# LCD-43.net
KiCad netlist of a schematic drawn in Altium Designer
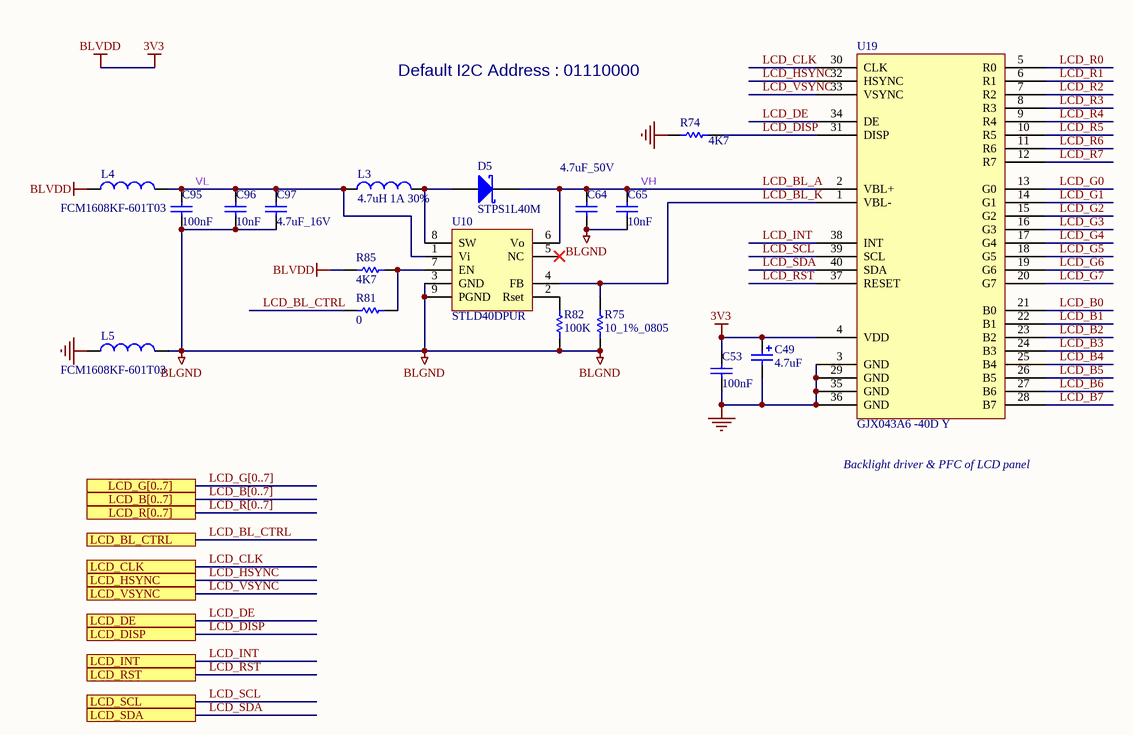
[diagram p0: LCD-43.SchDoc]

(export (version "E")
  (design (tool "Eeschema 10.0.6"))
  (components
    (comp (ref "C49")
      (value "4.7uF")
      (footprint "TAN-A")
      (description "Polarized Capacitor,4.7uF,16V,10%,typeA,AVX")
      (libsource (lib "MCD_TOOLS") (part "Cap_4.7uF_POL_10%_TANA"))
    )
    (comp (ref "C53")
      (value "100nF")
      (footprint "0402C")
      (description "Capacitor,100nF,16V,X7R,10%,0402,YAGEO")
      (libsource (lib "MCD_TOOLS") (part "Cap_100nF_X7R_10%_0402"))
    )
    (comp (ref "C64")
      (value "4.7uF_50V")
      (footprint "1206C")
      (description "Capacitor,4.7uF,50V, X7R,10%,1206,AVX")
      (libsource (lib "MCD_TOOLS") (part "Cap_4.7uF_X7R_10%_1206"))
    )
    (comp (ref "C65")
      (value "10nF")
      (footprint "0603C")
      (description "Capacitor,10nF,50V,X7R,10%,0603,YAGEO")
      (libsource (lib "MCD_TOOLS") (part "Cap_10nF_X7R_10%_0603"))
    )
    (comp (ref "C95")
      (value "100nF")
      (footprint "0603C")
      (description "Capacitor,100nF,16V,X7R,10%,0603,YAGEO")
      (libsource (lib "MCD_TOOLS") (part "Cap_100nF_X7R_10%_0603"))
    )
    (comp (ref "C96")
      (value "10nF")
      (footprint "0603C")
      (description "Capacitor,10nF,50V,X7R,10%,0603,YAGEO")
      (libsource (lib "MCD_TOOLS") (part "Cap_10nF_X7R_10%_0603"))
    )
    (comp (ref "C97")
      (value "4.7uF_16V")
      (footprint "1206C")
      (description "Capacitor,4.7uF,16V, X5R,10%,1206,AVX")
      (libsource (lib "MCD_TOOLS") (part "Cap_4.7uF_X5R_10%_1206"))
    )
    (comp (ref "D5")
      (value "STPS1L40M")
      (footprint "DO216-AA")
      (description "Low Drop power Schottky rectifier(1A, 40V, 0.4V)")
      (libsource (lib "MCD_TOOLS") (part "STPS1L40M"))
    )
    (comp (ref "L3")
      (value "4.7uH 1A 30%")
      (footprint "1210L")
      (description "FIXED IND 4.7UH 1A 180 MOHM 30% SMD")
      (libsource (lib "MCD_TOOLS") (part "Ind_4.7uH_1A_30%"))
    )
    (comp (ref "L4")
      (value "FCM1608KF-601T03")
      (footprint "0603L")
      (description "Bead,600R,350mA,0603,FCM1608KF-601T03,Tai-tech")
      (libsource (lib "MCD_TOOLS") (part "BEAD_600R_350MA_0603"))
    )
    (comp (ref "L5")
      (value "FCM1608KF-601T03")
      (footprint "0603L")
      (description "Bead,600R,350mA,0603,FCM1608KF-601T03,Tai-tech")
      (libsource (lib "MCD_TOOLS") (part "BEAD_600R_350MA_0603"))
    )
    (comp (ref "R74")
      (value "4K7")
      (footprint "0402R")
      (description "Resistor,4K7,0402,1%,YAGEO")
      (libsource (lib "MCD_TOOLS") (part "Res_4K7_1%_0402"))
    )
    (comp (ref "R75")
      (value "10_1%_0805")
      (footprint "0805R")
      (description "Resistor,10,0805,1%,Stackpole,1/4W")
      (libsource (lib "MCD_TOOLS") (part "Res_10_1%_0805"))
    )
    (comp (ref "R81")
      (value "0")
      (footprint "0402R")
      (description "Resistor,0,0402,5%,YAGEO")
      (libsource (lib "MCD_TOOLS") (part "Res_0_5%_0402"))
    )
    (comp (ref "R82")
      (value "100K")
      (footprint "0402R")
      (description "Resistor,100K,0402,1%,YAGEO")
      (libsource (lib "MCD_TOOLS") (part "Res_100K_1%_0402"))
    )
    (comp (ref "R85")
      (value "4K7")
      (footprint "0402R")
      (description "Resistor,4K7,0402,1%,YAGEO")
      (libsource (lib "MCD_TOOLS") (part "Res_4K7_1%_0402"))
    )
    (comp (ref "U10")
      (value "STLD40DPUR")
      (footprint "QFN8_0R65_3X3_ST")
      (description "White LED power supply for large display backlight, QFN8")
      (libsource (lib "MCD_TOOLS") (part "STLD40DPUR"))
    )
    (comp (ref "U19")
      (value "GJX043A6 -40D Y")
      (footprint "LCD_Kunjian_ HT043C_40P_P080_FLEX_FOLDED")
      (description "4.3 inch TFT 480*272 pixels with LED Backlight and Capacitive touch panel, high luminance")
      (libsource (lib "Mb1191") (part "HT043C"))
    )
  )
  (nets
    (net (code "1") (name "/LCD_B0") (class "Default")
      (node (ref "U19") (pin "21") (pinfunction "B0_21") (pintype "passive"))
    )
    (net (code "2") (name "/LCD_B1") (class "Default")
      (node (ref "U19") (pin "22") (pinfunction "B1_22") (pintype "passive"))
    )
    (net (code "3") (name "/LCD_B2") (class "Default")
      (node (ref "U19") (pin "23") (pinfunction "B2_23") (pintype "passive"))
    )
    (net (code "4") (name "/LCD_B3") (class "Default")
      (node (ref "U19") (pin "24") (pinfunction "B3_24") (pintype "passive"))
    )
    (net (code "5") (name "/LCD_B4") (class "Default")
      (node (ref "U19") (pin "25") (pinfunction "B4_25") (pintype "passive"))
    )
    (net (code "6") (name "/LCD_B5") (class "Default")
      (node (ref "U19") (pin "26") (pinfunction "B5_26") (pintype "passive"))
    )
    (net (code "7") (name "/LCD_B6") (class "Default")
      (node (ref "U19") (pin "27") (pinfunction "B6_27") (pintype "passive"))
    )
    (net (code "8") (name "/LCD_B7") (class "Default")
      (node (ref "U19") (pin "28") (pinfunction "B7_28") (pintype "passive"))
    )
    (net (code "9") (name "/LCD_BL_A") (class "Default")
      (node (ref "C64") (pin "1") (pinfunction "1_1") (pintype "passive"))
      (node (ref "C65") (pin "2") (pinfunction "2_2") (pintype "passive"))
      (node (ref "D5") (pin "2") (pinfunction "K_2") (pintype "passive"))
      (node (ref "U10") (pin "6") (pinfunction "Vo_6") (pintype "passive"))
      (node (ref "U19") (pin "2") (pinfunction "VBL+_2") (pintype "passive"))
    )
    (net (code "10") (name "/LCD_BL_CTRL") (class "Default")
      (node (ref "R81") (pin "2") (pinfunction "2_2") (pintype "passive"))
    )
    (net (code "11") (name "/LCD_BL_K") (class "Default")
      (node (ref "R75") (pin "2") (pinfunction "2_2") (pintype "passive"))
      (node (ref "U10") (pin "4") (pinfunction "FB_4") (pintype "passive"))
      (node (ref "U19") (pin "1") (pinfunction "VBL-_1") (pintype "passive"))
    )
    (net (code "13") (name "/LCD_CLK") (class "Default")
      (node (ref "U19") (pin "30") (pinfunction "CLK_30") (pintype "passive"))
    )
    (net (code "14") (name "/LCD_DE") (class "Default")
      (node (ref "U19") (pin "34") (pinfunction "DE_34") (pintype "passive"))
    )
    (net (code "15") (name "/LCD_DISP") (class "Default")
      (node (ref "R74") (pin "1") (pinfunction "1_1") (pintype "passive"))
      (node (ref "U19") (pin "31") (pinfunction "DISP_31") (pintype "passive"))
    )
    (net (code "16") (name "/LCD_G0") (class "Default")
      (node (ref "U19") (pin "13") (pinfunction "G0_13") (pintype "passive"))
    )
    (net (code "17") (name "/LCD_G1") (class "Default")
      (node (ref "U19") (pin "14") (pinfunction "G1_14") (pintype "passive"))
    )
    (net (code "18") (name "/LCD_G2") (class "Default")
      (node (ref "U19") (pin "15") (pinfunction "G2_15") (pintype "passive"))
    )
    (net (code "19") (name "/LCD_G3") (class "Default")
      (node (ref "U19") (pin "16") (pinfunction "G3_16") (pintype "passive"))
    )
    (net (code "20") (name "/LCD_G4") (class "Default")
      (node (ref "U19") (pin "17") (pinfunction "G4_17") (pintype "passive"))
    )
    (net (code "21") (name "/LCD_G5") (class "Default")
      (node (ref "U19") (pin "18") (pinfunction "G5_18") (pintype "passive"))
    )
    (net (code "22") (name "/LCD_G6") (class "Default")
      (node (ref "U19") (pin "19") (pinfunction "G6_19") (pintype "passive"))
    )
    (net (code "23") (name "/LCD_G7") (class "Default")
      (node (ref "U19") (pin "20") (pinfunction "G7_20") (pintype "passive"))
    )
    (net (code "25") (name "/LCD_HSYNC") (class "Default")
      (node (ref "U19") (pin "32") (pinfunction "HSYNC_32") (pintype "passive"))
    )
    (net (code "26") (name "/LCD_INT") (class "Default")
      (node (ref "U19") (pin "38") (pinfunction "INT_38") (pintype "passive"))
    )
    (net (code "27") (name "/LCD_R0") (class "Default")
      (node (ref "U19") (pin "5") (pinfunction "R0_5") (pintype "passive"))
    )
    (net (code "28") (name "/LCD_R1") (class "Default")
      (node (ref "U19") (pin "6") (pinfunction "R1_6") (pintype "passive"))
    )
    (net (code "29") (name "/LCD_R2") (class "Default")
      (node (ref "U19") (pin "7") (pinfunction "R2_7") (pintype "passive"))
    )
    (net (code "30") (name "/LCD_R3") (class "Default")
      (node (ref "U19") (pin "8") (pinfunction "R3_8") (pintype "passive"))
    )
    (net (code "31") (name "/LCD_R4") (class "Default")
      (node (ref "U19") (pin "9") (pinfunction "R4_9") (pintype "passive"))
    )
    (net (code "32") (name "/LCD_R5") (class "Default")
      (node (ref "U19") (pin "10") (pinfunction "R5_10") (pintype "passive"))
    )
    (net (code "33") (name "/LCD_R6") (class "Default")
      (node (ref "U19") (pin "11") (pinfunction "R6_11") (pintype "passive"))
    )
    (net (code "34") (name "/LCD_R7") (class "Default")
      (node (ref "U19") (pin "12") (pinfunction "R7_12") (pintype "passive"))
    )
    (net (code "35") (name "/LCD_RST") (class "Default")
      (node (ref "U19") (pin "37") (pinfunction "RESET_37") (pintype "passive"))
    )
    (net (code "37") (name "/LCD_SCL") (class "Default")
      (node (ref "U19") (pin "39") (pinfunction "SCL_39") (pintype "passive"))
    )
    (net (code "38") (name "/LCD_SDA") (class "Default")
      (node (ref "U19") (pin "40") (pinfunction "SDA_40") (pintype "passive"))
    )
    (net (code "39") (name "/LCD_VSYNC") (class "Default")
      (node (ref "U19") (pin "33") (pinfunction "VSYNC_33") (pintype "passive"))
    )
    (net (code "40") (name "/VL") (class "Default")
      (node (ref "C95") (pin "2") (pinfunction "2_2") (pintype "passive"))
      (node (ref "C96") (pin "2") (pinfunction "2_2") (pintype "passive"))
      (node (ref "C97") (pin "1") (pinfunction "1_1") (pintype "passive"))
      (node (ref "L3") (pin "1") (pinfunction "1_1") (pintype "passive"))
      (node (ref "L4") (pin "2") (pinfunction "2_2") (pintype "passive"))
      (node (ref "U10") (pin "1") (pinfunction "Vi_1") (pintype "passive"))
    )
    (net (code "41") (name "3V3") (class "Default")
      (node (ref "C49") (pin "1") (pinfunction "1_1") (pintype "passive"))
      (node (ref "C53") (pin "2") (pinfunction "2_2") (pintype "passive"))
      (node (ref "L4") (pin "1") (pinfunction "1_1") (pintype "passive"))
      (node (ref "R85") (pin "2") (pinfunction "2_2") (pintype "passive"))
      (node (ref "U19") (pin "4") (pinfunction "VDD_4") (pintype "passive"))
    )
    (net (code "42") (name "BLGND") (class "Default")
      (node (ref "C64") (pin "2") (pinfunction "2_2") (pintype "passive"))
      (node (ref "C65") (pin "1") (pinfunction "1_1") (pintype "passive"))
      (node (ref "C95") (pin "1") (pinfunction "1_1") (pintype "passive"))
      (node (ref "C96") (pin "1") (pinfunction "1_1") (pintype "passive"))
      (node (ref "C97") (pin "2") (pinfunction "2_2") (pintype "passive"))
      (node (ref "L5") (pin "2") (pinfunction "2_2") (pintype "passive"))
      (node (ref "R75") (pin "1") (pinfunction "1_1") (pintype "passive"))
      (node (ref "R82") (pin "2") (pinfunction "2_2") (pintype "passive"))
      (node (ref "U10") (pin "3") (pinfunction "GND_3") (pintype "passive"))
      (node (ref "U10") (pin "9") (pinfunction "PGND_9") (pintype "passive"))
    )
    (net (code "43") (name "GND") (class "Default")
      (node (ref "C49") (pin "2") (pinfunction "2_2") (pintype "passive"))
      (node (ref "C53") (pin "1") (pinfunction "1_1") (pintype "passive"))
      (node (ref "L5") (pin "1") (pinfunction "1_1") (pintype "passive"))
      (node (ref "R74") (pin "2") (pinfunction "2_2") (pintype "passive"))
      (node (ref "U19") (pin "29") (pinfunction "GND_29") (pintype "passive"))
      (node (ref "U19") (pin "3") (pinfunction "GND_3") (pintype "passive"))
      (node (ref "U19") (pin "35") (pinfunction "GND_35") (pintype "passive"))
      (node (ref "U19") (pin "36") (pinfunction "GND_36") (pintype "passive"))
    )
    (net (code "44") (name "Net-(D5-A)") (class "Default")
      (node (ref "D5") (pin "1") (pinfunction "A_1") (pintype "passive"))
      (node (ref "L3") (pin "2") (pinfunction "2_2") (pintype "passive"))
      (node (ref "U10") (pin "8") (pinfunction "SW_8") (pintype "passive"))
    )
    (net (code "45") (name "Net-(U10-EN)") (class "Default")
      (node (ref "R81") (pin "1") (pinfunction "1_1") (pintype "passive"))
      (node (ref "R85") (pin "1") (pinfunction "1_1") (pintype "passive"))
      (node (ref "U10") (pin "7") (pinfunction "EN_7") (pintype "passive"))
    )
    (net (code "46") (name "Net-(U10-Rset)") (class "Default")
      (node (ref "R82") (pin "1") (pinfunction "1_1") (pintype "passive"))
      (node (ref "U10") (pin "2") (pinfunction "Rset_2") (pintype "passive"))
    )
    (net (code "47") (name "unconnected-(U10-NC-Pad5)") (class "Default")
      (node (ref "U10") (pin "5") (pinfunction "NC_5") (pintype "passive+no_connect"))
    )
  )
)
